# MotorCtrl.net
KiCad netlist of a schematic drawn in Altium Designer
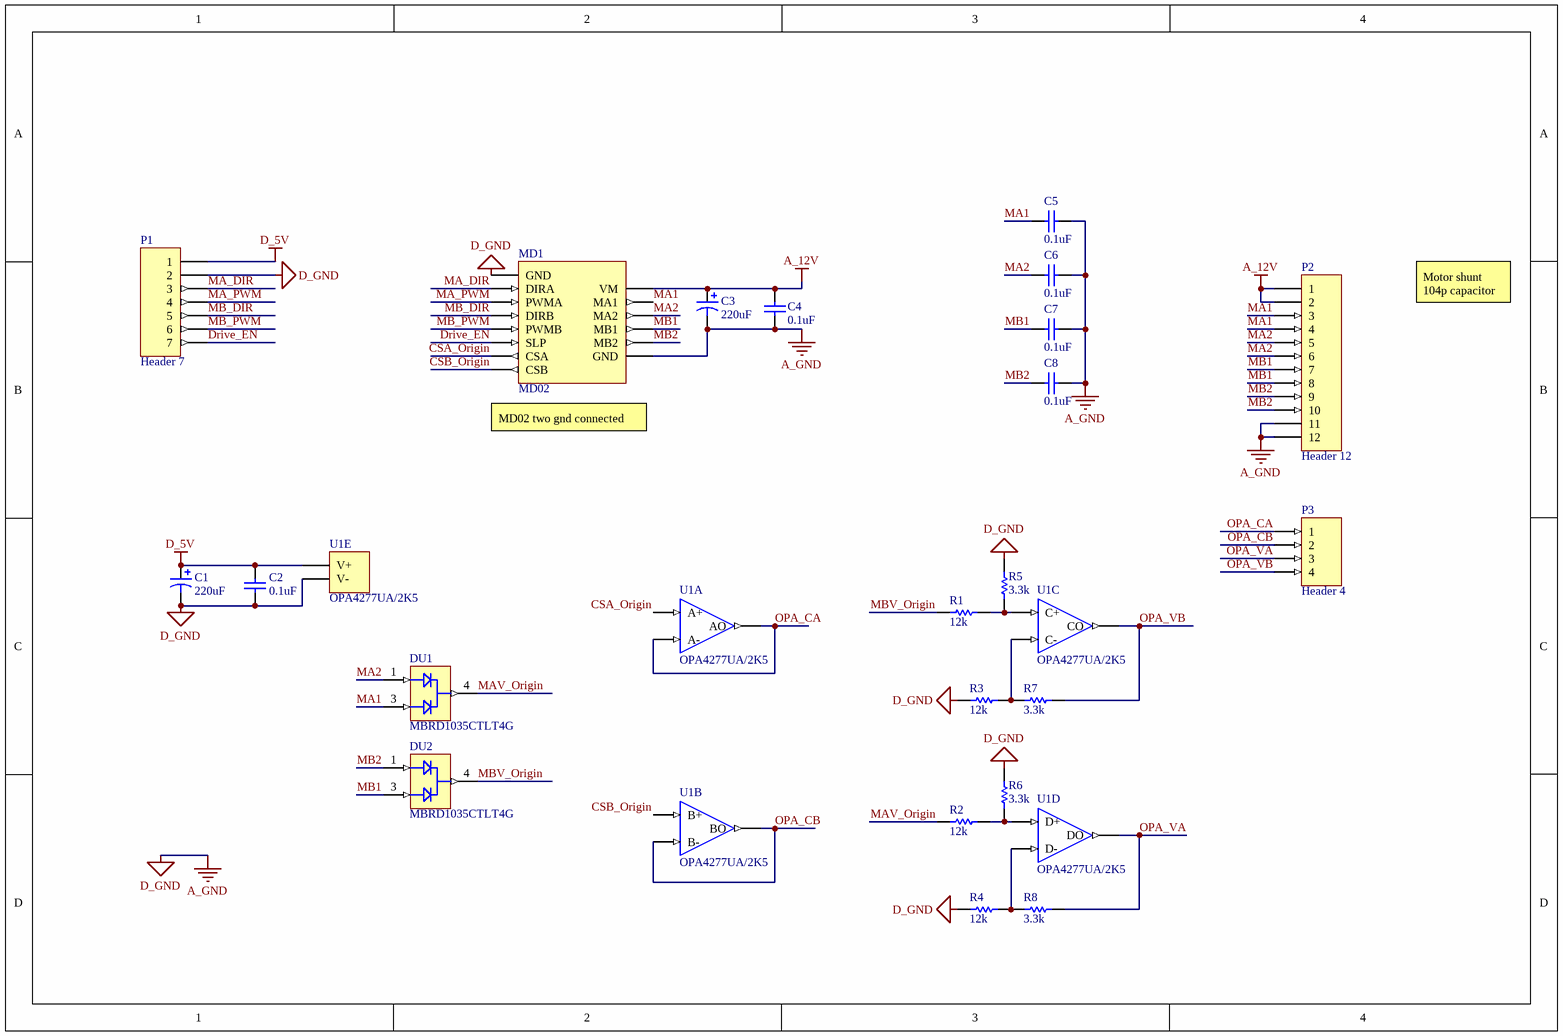
[diagram p0: MotorCtrl.SchDoc]

(export (version "E")
  (design (tool "Eeschema 10.0.6"))
  (components
    (comp (ref "C1")
      (value "220uF")
      (footprint "OWMR:VZT221M1ETR-0607")
      (fields (field (name "PUBLISHER") "Altium Limited"))
      (libsource (lib "Miscellaneous Devices") (part "Cap Pol1"))
    )
    (comp (ref "C2")
      (value "0.1uF")
      (footprint "OWMR:CL10B104KA8NNNC")
      (description "25V 100nF X7R ±10% 0603  Multilayer Ceramic Capacitors MLCC - SMD/SMT ROHS")
      (fields (field (name "PUBLISHER") "Altium Limited"))
      (libsource (lib "Miscellaneous Devices") (part "Cap Semi"))
    )
    (comp (ref "C3")
      (value "220uF")
      (footprint "OWMR:VZT221M1ETR-0607")
      (fields (field (name "PUBLISHER") "Altium Limited"))
      (libsource (lib "Miscellaneous Devices") (part "Cap Pol1"))
    )
    (comp (ref "C4")
      (value "0.1uF")
      (footprint "OWMR:1210B104K500NT")
      (description "50V 100nF X7R ±10% 1210  Multilayer Ceramic Capacitors MLCC - SMD/SMT ROHS")
      (fields (field (name "PUBLISHER") "Altium Limited"))
      (libsource (lib "Miscellaneous Devices") (part "Cap Semi"))
    )
    (comp (ref "C5")
      (value "0.1uF")
      (footprint "OWMR:1210B104K500NT")
      (description "50V 100nF X7R ±10% 1210  Multilayer Ceramic Capacitors MLCC - SMD/SMT ROHS")
      (fields (field (name "PUBLISHER") "Altium Limited"))
      (libsource (lib "Miscellaneous Devices") (part "Cap Semi"))
    )
    (comp (ref "C6")
      (value "0.1uF")
      (footprint "OWMR:1210B104K500NT")
      (description "50V 100nF X7R ±10% 1210  Multilayer Ceramic Capacitors MLCC - SMD/SMT ROHS")
      (fields (field (name "PUBLISHER") "Altium Limited"))
      (libsource (lib "Miscellaneous Devices") (part "Cap Semi"))
    )
    (comp (ref "C7")
      (value "0.1uF")
      (footprint "OWMR:1210B104K500NT")
      (description "50V 100nF X7R ±10% 1210  Multilayer Ceramic Capacitors MLCC - SMD/SMT ROHS")
      (fields (field (name "PUBLISHER") "Altium Limited"))
      (libsource (lib "Miscellaneous Devices") (part "Cap Semi"))
    )
    (comp (ref "C8")
      (value "0.1uF")
      (footprint "OWMR:1210B104K500NT")
      (description "50V 100nF X7R ±10% 1210  Multilayer Ceramic Capacitors MLCC - SMD/SMT ROHS")
      (fields (field (name "PUBLISHER") "Altium Limited"))
      (libsource (lib "Miscellaneous Devices") (part "Cap Semi"))
    )
    (comp (ref "DU1")
      (value "MBRD1035CTLT4G")
      (footprint "OWMR:MBRD1035CTLT4G")
      (description "35V 470mV@5A 5A TO-252-2(DPAK) Schottky Barrier Diodes (SBD) ROHS")
      (libsource (lib "OWMR") (part "MBRD1035CTLT4G"))
    )
    (comp (ref "DU2")
      (value "MBRD1035CTLT4G")
      (footprint "OWMR:MBRD1035CTLT4G")
      (description "35V 470mV@5A 5A TO-252-2(DPAK) Schottky Barrier Diodes (SBD) ROHS")
      (libsource (lib "OWMR") (part "MBRD1035CTLT4G"))
    )
    (comp (ref "MD1")
      (value "MD02")
      (footprint "OWMR:MD02")
      (description "MD02 17A 2 cheel motor driver")
      (libsource (lib "OWMR") (part "MD02 Motor Driver"))
    )
    (comp (ref "P1")
      (value "Header 7")
      (footprint "OWMR:KH-2.54PH180-1X7P-L11.5")
      (fields (field (name "PUBLISHER") "Altium Limited"))
      (libsource (lib "Miscellaneous Connectors") (part "Header 7"))
    )
    (comp (ref "P2")
      (value "Header 12")
      (footprint "OWMR:KH-2.54PH180-1X12P-L11.5 (Pad Linked)")
      (fields (field (name "PUBLISHER") "Altium Limited"))
      (libsource (lib "Miscellaneous Connectors") (part "Header 12"))
    )
    (comp (ref "P3")
      (value "Header 4")
      (footprint "OWMR:KH-2.54PH180-1X4P-L11.5")
      (fields (field (name "PUBLISHER") "Altium Limited"))
      (libsource (lib "Miscellaneous Connectors") (part "Header 4"))
    )
    (comp (ref "R1")
      (value "12k")
      (footprint "OWMR:PTFR0603B12K0N9")
      (description "Resistor")
      (fields (field (name "PUBLISHER") "Altium Limited"))
      (libsource (lib "Miscellaneous Devices") (part "Res1"))
    )
    (comp (ref "R2")
      (value "12k")
      (footprint "OWMR:PTFR0603B12K0N9")
      (description "Resistor")
      (fields (field (name "PUBLISHER") "Altium Limited"))
      (libsource (lib "Miscellaneous Devices") (part "Res1"))
    )
    (comp (ref "R3")
      (value "12k")
      (footprint "OWMR:PTFR0603B12K0N9")
      (description "Resistor")
      (fields (field (name "PUBLISHER") "Altium Limited"))
      (libsource (lib "Miscellaneous Devices") (part "Res1"))
    )
    (comp (ref "R4")
      (value "12k")
      (footprint "OWMR:PTFR0603B12K0N9")
      (description "Resistor")
      (fields (field (name "PUBLISHER") "Altium Limited"))
      (libsource (lib "Miscellaneous Devices") (part "Res1"))
    )
    (comp (ref "R5")
      (value "3.3k")
      (footprint "OWMR:0603WAF3301T5E")
      (description "Resistor")
      (fields (field (name "PUBLISHER") "Altium Limited"))
      (libsource (lib "Miscellaneous Devices") (part "Res1"))
    )
    (comp (ref "R6")
      (value "3.3k")
      (footprint "OWMR:0603WAF3301T5E")
      (description "Resistor")
      (fields (field (name "PUBLISHER") "Altium Limited"))
      (libsource (lib "Miscellaneous Devices") (part "Res1"))
    )
    (comp (ref "R7")
      (value "3.3k")
      (footprint "OWMR:0603WAF3301T5E")
      (description "Resistor")
      (fields (field (name "PUBLISHER") "Altium Limited"))
      (libsource (lib "Miscellaneous Devices") (part "Res1"))
    )
    (comp (ref "R8")
      (value "3.3k")
      (footprint "OWMR:0603WAF3301T5E")
      (description "Resistor")
      (fields (field (name "PUBLISHER") "Altium Limited"))
      (libsource (lib "Miscellaneous Devices") (part "Res1"))
    )
    (comp (ref "U1")
      (value "OPA4277UA/2K5")
      (footprint "OWMR:OPA4277UA/2K5")
      (description "790μA 1MHz 4 4V~36V,±2V~18V 0.8 V/us General Purpose SOIC-14  Precision OpAmps ROHS")
      (libsource (lib "") (part "OPA4277UA/2K5_1"))
    )
  )
  (nets
    (net (code "1") (name "/CSA_Origin") (class "Default")
      (node (ref "MD1") (pin "7") (pinfunction "CSA_7") (pintype "output"))
      (node (ref "U1") (pin "3") (pinfunction "A+_3") (pintype "input"))
    )
    (net (code "2") (name "/CSB_Origin") (class "Default")
      (node (ref "MD1") (pin "8") (pinfunction "CSB_8") (pintype "output"))
      (node (ref "U1") (pin "5") (pinfunction "B+_5") (pintype "input"))
    )
    (net (code "3") (name "/Drive_EN") (class "Default")
      (node (ref "MD1") (pin "6") (pinfunction "SLP_6") (pintype "input"))
      (node (ref "P1") (pin "7") (pinfunction "7_7") (pintype "output"))
    )
    (net (code "4") (name "/MA1") (class "Default")
      (node (ref "C5") (pin "1") (pinfunction "1_1") (pintype "passive"))
      (node (ref "DU1") (pin "3") (pinfunction "3_3") (pintype "input"))
      (node (ref "MD1") (pin "10") (pinfunction "MA1_10") (pintype "output"))
      (node (ref "P2") (pin "3") (pinfunction "3_3") (pintype "input"))
      (node (ref "P2") (pin "4") (pinfunction "4_4") (pintype "input"))
    )
    (net (code "5") (name "/MA2") (class "Default")
      (node (ref "C6") (pin "1") (pinfunction "1_1") (pintype "passive"))
      (node (ref "DU1") (pin "1") (pinfunction "1_1") (pintype "input"))
      (node (ref "MD1") (pin "11") (pinfunction "MA2_11") (pintype "output"))
      (node (ref "P2") (pin "5") (pinfunction "5_5") (pintype "input"))
      (node (ref "P2") (pin "6") (pinfunction "6_6") (pintype "input"))
    )
    (net (code "6") (name "/MAV_Origin") (class "Default")
      (node (ref "DU1") (pin "4") (pinfunction "4_4") (pintype "output"))
      (node (ref "R2") (pin "2") (pinfunction "2_2") (pintype "passive"))
    )
    (net (code "7") (name "/MA_DIR") (class "Default")
      (node (ref "MD1") (pin "2") (pinfunction "DIRA_2") (pintype "input"))
      (node (ref "P1") (pin "3") (pinfunction "3_3") (pintype "output"))
    )
    (net (code "8") (name "/MA_PWM") (class "Default")
      (node (ref "MD1") (pin "3") (pinfunction "PWMA_3") (pintype "input"))
      (node (ref "P1") (pin "4") (pinfunction "4_4") (pintype "output"))
    )
    (net (code "9") (name "/MB1") (class "Default")
      (node (ref "C7") (pin "1") (pinfunction "1_1") (pintype "passive"))
      (node (ref "DU2") (pin "3") (pinfunction "3_3") (pintype "input"))
      (node (ref "MD1") (pin "12") (pinfunction "MB1_12") (pintype "output"))
      (node (ref "P2") (pin "7") (pinfunction "7_7") (pintype "input"))
      (node (ref "P2") (pin "8") (pinfunction "8_8") (pintype "input"))
    )
    (net (code "10") (name "/MB2") (class "Default")
      (node (ref "C8") (pin "1") (pinfunction "1_1") (pintype "passive"))
      (node (ref "DU2") (pin "1") (pinfunction "1_1") (pintype "input"))
      (node (ref "MD1") (pin "13") (pinfunction "MB2_13") (pintype "output"))
      (node (ref "P2") (pin "10") (pinfunction "10_10") (pintype "input"))
      (node (ref "P2") (pin "9") (pinfunction "9_9") (pintype "input"))
    )
    (net (code "11") (name "/MBV_Origin") (class "Default")
      (node (ref "DU2") (pin "4") (pinfunction "4_4") (pintype "output"))
      (node (ref "R1") (pin "2") (pinfunction "2_2") (pintype "passive"))
    )
    (net (code "12") (name "/MB_DIR") (class "Default")
      (node (ref "MD1") (pin "4") (pinfunction "DIRB_4") (pintype "input"))
      (node (ref "P1") (pin "5") (pinfunction "5_5") (pintype "output"))
    )
    (net (code "13") (name "/MB_PWM") (class "Default")
      (node (ref "MD1") (pin "5") (pinfunction "PWMB_5") (pintype "input"))
      (node (ref "P1") (pin "6") (pinfunction "6_6") (pintype "output"))
    )
    (net (code "14") (name "/OPA_CA") (class "Default")
      (node (ref "P3") (pin "1") (pinfunction "1_1") (pintype "input"))
      (node (ref "U1") (pin "1") (pinfunction "AO_1") (pintype "output"))
      (node (ref "U1") (pin "2") (pinfunction "A-_2") (pintype "input"))
    )
    (net (code "15") (name "/OPA_CB") (class "Default")
      (node (ref "P3") (pin "2") (pinfunction "2_2") (pintype "input"))
      (node (ref "U1") (pin "6") (pinfunction "B-_6") (pintype "input"))
      (node (ref "U1") (pin "7") (pinfunction "BO_7") (pintype "output"))
    )
    (net (code "16") (name "/OPA_VA") (class "Default")
      (node (ref "P3") (pin "3") (pinfunction "3_3") (pintype "input"))
      (node (ref "R8") (pin "1") (pinfunction "1_1") (pintype "passive"))
      (node (ref "U1") (pin "14") (pinfunction "DO_14") (pintype "output"))
    )
    (net (code "17") (name "/OPA_VB") (class "Default")
      (node (ref "P3") (pin "4") (pinfunction "4_4") (pintype "input"))
      (node (ref "R7") (pin "1") (pinfunction "1_1") (pintype "passive"))
      (node (ref "U1") (pin "8") (pinfunction "CO_8") (pintype "output"))
    )
    (net (code "18") (name "A_12V") (class "Default")
      (node (ref "C3") (pin "1") (pinfunction "1_1") (pintype "passive"))
      (node (ref "C4") (pin "1") (pinfunction "1_1") (pintype "passive"))
      (node (ref "MD1") (pin "9") (pinfunction "VM_9") (pintype "power_in"))
      (node (ref "P2") (pin "1") (pinfunction "1_1") (pintype "power_in"))
      (node (ref "P2") (pin "2") (pinfunction "2_2") (pintype "power_in"))
    )
    (net (code "19") (name "A_GND") (class "Default")
      (node (ref "C1") (pin "2") (pinfunction "2_2") (pintype "passive"))
      (node (ref "C2") (pin "1") (pinfunction "1_1") (pintype "passive"))
      (node (ref "C3") (pin "2") (pinfunction "2_2") (pintype "passive"))
      (node (ref "C4") (pin "2") (pinfunction "2_2") (pintype "passive"))
      (node (ref "C5") (pin "2") (pinfunction "2_2") (pintype "passive"))
      (node (ref "C6") (pin "2") (pinfunction "2_2") (pintype "passive"))
      (node (ref "C7") (pin "2") (pinfunction "2_2") (pintype "passive"))
      (node (ref "C8") (pin "2") (pinfunction "2_2") (pintype "passive"))
      (node (ref "MD1") (pin "1") (pinfunction "GND_1") (pintype "power_in"))
      (node (ref "MD1") (pin "14") (pinfunction "GND_14") (pintype "passive"))
      (node (ref "P1") (pin "2") (pinfunction "2_2") (pintype "power_in"))
      (node (ref "P2") (pin "11") (pinfunction "11_11") (pintype "power_in"))
      (node (ref "P2") (pin "12") (pinfunction "12_12") (pintype "power_in"))
      (node (ref "R3") (pin "2") (pinfunction "2_2") (pintype "passive"))
      (node (ref "R4") (pin "2") (pinfunction "2_2") (pintype "passive"))
      (node (ref "R5") (pin "2") (pinfunction "2_2") (pintype "passive"))
      (node (ref "R6") (pin "2") (pinfunction "2_2") (pintype "passive"))
      (node (ref "U1") (pin "11") (pinfunction "V-_11") (pintype "power_in"))
    )
    (net (code "20") (name "D_5V") (class "Default")
      (node (ref "C1") (pin "1") (pinfunction "1_1") (pintype "passive"))
      (node (ref "C2") (pin "2") (pinfunction "2_2") (pintype "passive"))
      (node (ref "P1") (pin "1") (pinfunction "1_1") (pintype "power_in"))
      (node (ref "U1") (pin "4") (pinfunction "V+_4") (pintype "power_in"))
    )
    (net (code "21") (name "Net-(U1C-C+)") (class "Default")
      (node (ref "R1") (pin "1") (pinfunction "1_1") (pintype "passive"))
      (node (ref "R5") (pin "1") (pinfunction "1_1") (pintype "passive"))
      (node (ref "U1") (pin "10") (pinfunction "C+_10") (pintype "input"))
    )
    (net (code "22") (name "Net-(U1C-C-)") (class "Default")
      (node (ref "R3") (pin "1") (pinfunction "1_1") (pintype "passive"))
      (node (ref "R7") (pin "2") (pinfunction "2_2") (pintype "passive"))
      (node (ref "U1") (pin "9") (pinfunction "C-_9") (pintype "input"))
    )
    (net (code "23") (name "Net-(U1D-D+)") (class "Default")
      (node (ref "R2") (pin "1") (pinfunction "1_1") (pintype "passive"))
      (node (ref "R6") (pin "1") (pinfunction "1_1") (pintype "passive"))
      (node (ref "U1") (pin "12") (pinfunction "D+_12") (pintype "input"))
    )
    (net (code "24") (name "Net-(U1D-D-)") (class "Default")
      (node (ref "R4") (pin "1") (pinfunction "1_1") (pintype "passive"))
      (node (ref "R8") (pin "2") (pinfunction "2_2") (pintype "passive"))
      (node (ref "U1") (pin "13") (pinfunction "D-_13") (pintype "input"))
    )
  )
)
